# merci_main.net
KiCad netlist of a schematic drawn in Altium Designer
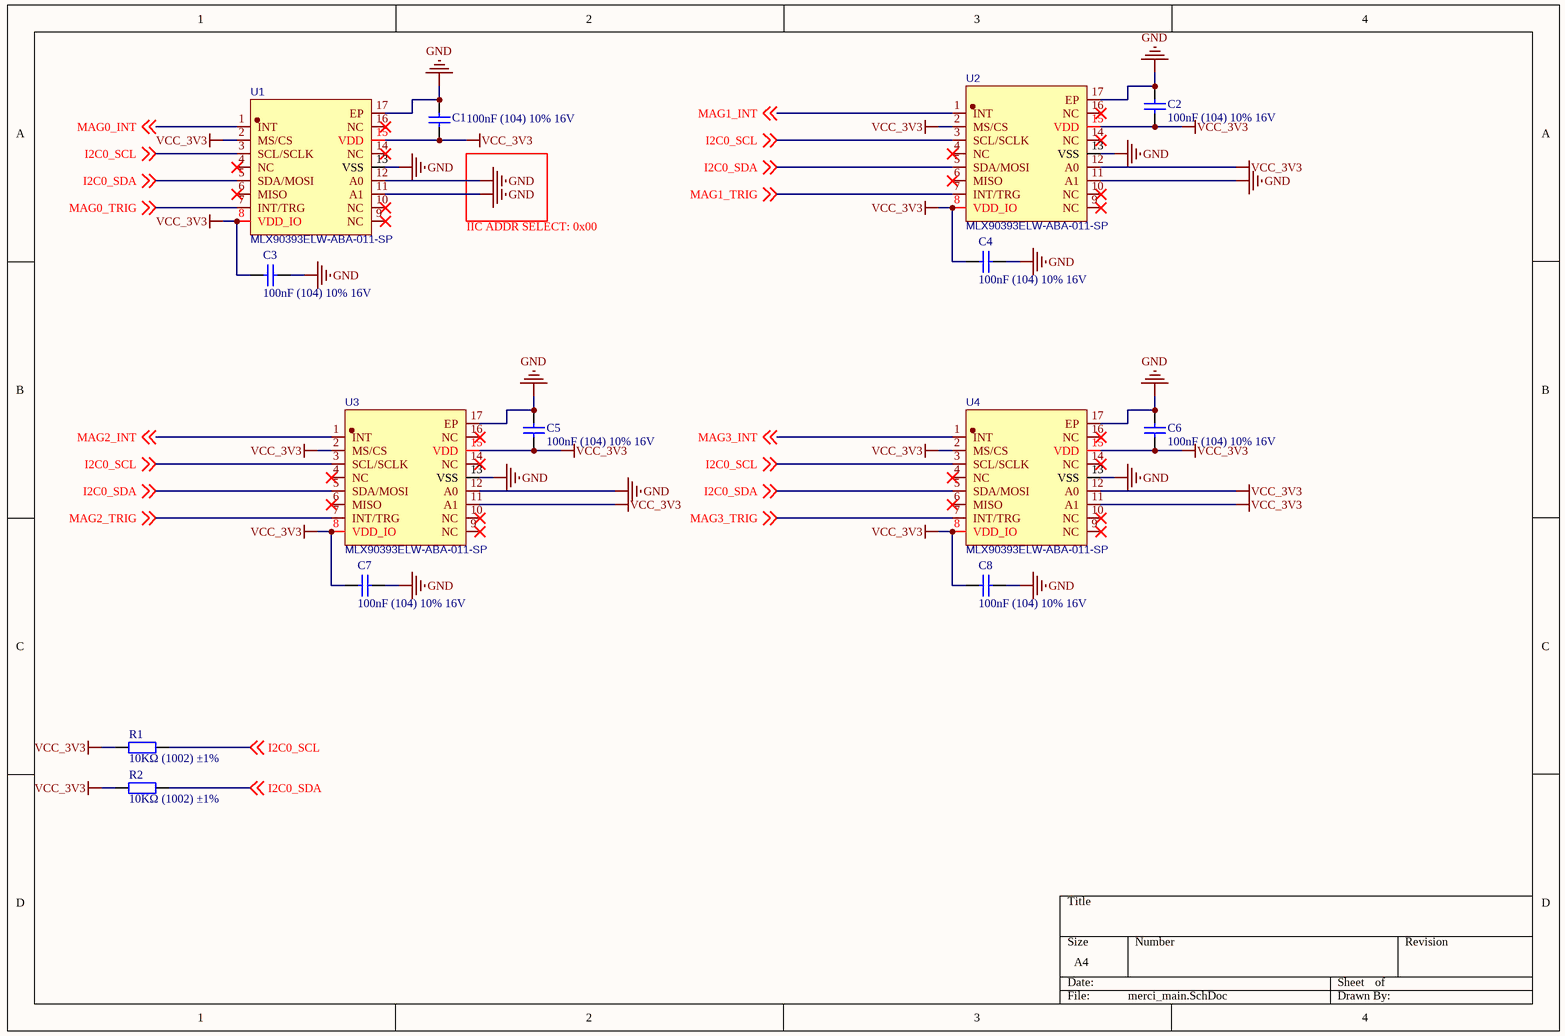
[diagram p0: merci_main.SchDoc]

(export (version "E")
  (design (tool "Eeschema 10.0.6"))
  (components
    (comp (ref "C1")
      (value "100nF (104) 10% 16V")
      (footprint "LC-0402_C_NOSILK")
      (description "贴片电容")
      (libsource (lib "Miscellaneous Devices LC") (part "0402 100nF (104) 10% 16V"))
    )
    (comp (ref "C2")
      (value "100nF (104) 10% 16V")
      (footprint "LC-0402_C_NOSILK")
      (description "贴片电容")
      (libsource (lib "Miscellaneous Devices LC") (part "0402 100nF (104) 10% 16V"))
    )
    (comp (ref "C3")
      (value "100nF (104) 10% 16V")
      (footprint "LC-0402_C_NOSILK")
      (description "贴片电容")
      (libsource (lib "Miscellaneous Devices LC") (part "0402 100nF (104) 10% 16V"))
    )
    (comp (ref "C4")
      (value "100nF (104) 10% 16V")
      (footprint "LC-0402_C_NOSILK")
      (description "贴片电容")
      (libsource (lib "Miscellaneous Devices LC") (part "0402 100nF (104) 10% 16V"))
    )
    (comp (ref "C5")
      (value "100nF (104) 10% 16V")
      (footprint "LC-0402_C_NOSILK")
      (description "贴片电容")
      (libsource (lib "Miscellaneous Devices LC") (part "0402 100nF (104) 10% 16V"))
    )
    (comp (ref "C6")
      (value "100nF (104) 10% 16V")
      (footprint "LC-0402_C_NOSILK")
      (description "贴片电容")
      (libsource (lib "Miscellaneous Devices LC") (part "0402 100nF (104) 10% 16V"))
    )
    (comp (ref "C7")
      (value "100nF (104) 10% 16V")
      (footprint "LC-0402_C_NOSILK")
      (description "贴片电容")
      (libsource (lib "Miscellaneous Devices LC") (part "0402 100nF (104) 10% 16V"))
    )
    (comp (ref "C8")
      (value "100nF (104) 10% 16V")
      (footprint "LC-0402_C_NOSILK")
      (description "贴片电容")
      (libsource (lib "Miscellaneous Devices LC") (part "0402 100nF (104) 10% 16V"))
    )
    (comp (ref "R1")
      (value "10KΩ (1002) ±1%")
      (footprint "LC-0402_R_NOSILK")
      (description "贴片电阻")
      (libsource (lib "Miscellaneous Devices LC") (part "0402 10KΩ (1002) 1%"))
    )
    (comp (ref "R2")
      (value "10KΩ (1002) ±1%")
      (footprint "LC-0402_R_NOSILK")
      (description "贴片电阻")
      (libsource (lib "Miscellaneous Devices LC") (part "0402 10KΩ (1002) 1%"))
    )
    (comp (ref "U1")
      (value "MLX90393ELW-ABA-011-SP")
      (footprint "QFN-16_L3.0-W3.0-P0.50-TR-EP1.7")
      (fields (field (name "BOM_SUPPLIER PART") "C1526586") (field (name "CONTRIBUTOR") "LCSC"))
      (libsource (lib "merci") (part "MLX90393ELW-ABA-011-SP"))
    )
    (comp (ref "U2")
      (value "MLX90393ELW-ABA-011-SP")
      (footprint "QFN-16_L3.0-W3.0-P0.50-TR-EP1.7")
      (fields (field (name "BOM_SUPPLIER PART") "C1526586") (field (name "CONTRIBUTOR") "LCSC"))
      (libsource (lib "merci") (part "MLX90393ELW-ABA-011-SP"))
    )
    (comp (ref "U3")
      (value "MLX90393ELW-ABA-011-SP")
      (footprint "QFN-16_L3.0-W3.0-P0.50-TR-EP1.7")
      (fields (field (name "BOM_SUPPLIER PART") "C1526586") (field (name "CONTRIBUTOR") "LCSC"))
      (libsource (lib "merci") (part "MLX90393ELW-ABA-011-SP"))
    )
    (comp (ref "U4")
      (value "MLX90393ELW-ABA-011-SP")
      (footprint "QFN-16_L3.0-W3.0-P0.50-TR-EP1.7")
      (fields (field (name "BOM_SUPPLIER PART") "C1526586") (field (name "CONTRIBUTOR") "LCSC"))
      (libsource (lib "merci") (part "MLX90393ELW-ABA-011-SP"))
    )
  )
  (nets
    (net (code "1") (name "GND") (class "Default")
      (node (ref "C1") (pin "2") (pinfunction "2_2") (pintype "passive"))
      (node (ref "C2") (pin "1") (pinfunction "1_1") (pintype "passive"))
      (node (ref "C3") (pin "1") (pinfunction "1_1") (pintype "passive"))
      (node (ref "C4") (pin "1") (pinfunction "1_1") (pintype "passive"))
      (node (ref "C5") (pin "2") (pinfunction "2_2") (pintype "passive"))
      (node (ref "C6") (pin "1") (pinfunction "1_1") (pintype "passive"))
      (node (ref "C7") (pin "1") (pinfunction "1_1") (pintype "passive"))
      (node (ref "C8") (pin "1") (pinfunction "1_1") (pintype "passive"))
      (node (ref "U1") (pin "11") (pinfunction "A1_11") (pintype "passive"))
      (node (ref "U1") (pin "12") (pinfunction "A0_12") (pintype "passive"))
      (node (ref "U1") (pin "13") (pinfunction "VSS_13") (pintype "passive"))
      (node (ref "U1") (pin "17") (pinfunction "EP_17") (pintype "passive"))
      (node (ref "U2") (pin "11") (pinfunction "A1_11") (pintype "passive"))
      (node (ref "U2") (pin "13") (pinfunction "VSS_13") (pintype "passive"))
      (node (ref "U2") (pin "17") (pinfunction "EP_17") (pintype "passive"))
      (node (ref "U3") (pin "12") (pinfunction "A0_12") (pintype "passive"))
      (node (ref "U3") (pin "13") (pinfunction "VSS_13") (pintype "passive"))
      (node (ref "U3") (pin "17") (pinfunction "EP_17") (pintype "passive"))
      (node (ref "U4") (pin "13") (pinfunction "VSS_13") (pintype "passive"))
      (node (ref "U4") (pin "17") (pinfunction "EP_17") (pintype "passive"))
    )
    (net (code "2") (name "I2C0_SCL") (class "Default")
      (node (ref "R1") (pin "2") (pinfunction "2_2") (pintype "passive"))
      (node (ref "U1") (pin "3") (pinfunction "SCL/SCLK_3") (pintype "passive"))
      (node (ref "U2") (pin "3") (pinfunction "SCL/SCLK_3") (pintype "passive"))
      (node (ref "U3") (pin "3") (pinfunction "SCL/SCLK_3") (pintype "passive"))
      (node (ref "U4") (pin "3") (pinfunction "SCL/SCLK_3") (pintype "passive"))
    )
    (net (code "3") (name "I2C0_SDA") (class "Default")
      (node (ref "R2") (pin "2") (pinfunction "2_2") (pintype "passive"))
      (node (ref "U1") (pin "5") (pinfunction "SDA/MOSI_5") (pintype "passive"))
      (node (ref "U2") (pin "5") (pinfunction "SDA/MOSI_5") (pintype "passive"))
      (node (ref "U3") (pin "5") (pinfunction "SDA/MOSI_5") (pintype "passive"))
      (node (ref "U4") (pin "5") (pinfunction "SDA/MOSI_5") (pintype "passive"))
    )
    (net (code "4") (name "MAG0_INT") (class "Default")
      (node (ref "U1") (pin "1") (pinfunction "INT_1") (pintype "passive"))
    )
    (net (code "5") (name "MAG0_TRIG") (class "Default")
      (node (ref "U1") (pin "7") (pinfunction "INT/TRG_7") (pintype "passive"))
    )
    (net (code "6") (name "MAG1_INT") (class "Default")
      (node (ref "U2") (pin "1") (pinfunction "INT_1") (pintype "passive"))
    )
    (net (code "7") (name "MAG1_TRIG") (class "Default")
      (node (ref "U2") (pin "7") (pinfunction "INT/TRG_7") (pintype "passive"))
    )
    (net (code "8") (name "MAG2_INT") (class "Default")
      (node (ref "U3") (pin "1") (pinfunction "INT_1") (pintype "passive"))
    )
    (net (code "9") (name "MAG2_TRIG") (class "Default")
      (node (ref "U3") (pin "7") (pinfunction "INT/TRG_7") (pintype "passive"))
    )
    (net (code "10") (name "MAG3_INT") (class "Default")
      (node (ref "U4") (pin "1") (pinfunction "INT_1") (pintype "passive"))
    )
    (net (code "11") (name "MAG3_TRIG") (class "Default")
      (node (ref "U4") (pin "7") (pinfunction "INT/TRG_7") (pintype "passive"))
    )
    (net (code "12") (name "VCC_3V3") (class "Default")
      (node (ref "C1") (pin "1") (pinfunction "1_1") (pintype "passive"))
      (node (ref "C2") (pin "2") (pinfunction "2_2") (pintype "passive"))
      (node (ref "C3") (pin "2") (pinfunction "2_2") (pintype "passive"))
      (node (ref "C4") (pin "2") (pinfunction "2_2") (pintype "passive"))
      (node (ref "C5") (pin "1") (pinfunction "1_1") (pintype "passive"))
      (node (ref "C6") (pin "2") (pinfunction "2_2") (pintype "passive"))
      (node (ref "C7") (pin "2") (pinfunction "2_2") (pintype "passive"))
      (node (ref "C8") (pin "2") (pinfunction "2_2") (pintype "passive"))
      (node (ref "R1") (pin "1") (pinfunction "1_1") (pintype "passive"))
      (node (ref "R2") (pin "1") (pinfunction "1_1") (pintype "passive"))
      (node (ref "U1") (pin "15") (pinfunction "VDD_15") (pintype "passive"))
      (node (ref "U1") (pin "2") (pinfunction "MS/CS_2") (pintype "passive"))
      (node (ref "U1") (pin "8") (pinfunction "VDD_IO_8") (pintype "passive"))
      (node (ref "U2") (pin "12") (pinfunction "A0_12") (pintype "passive"))
      (node (ref "U2") (pin "15") (pinfunction "VDD_15") (pintype "passive"))
      (node (ref "U2") (pin "2") (pinfunction "MS/CS_2") (pintype "passive"))
      (node (ref "U2") (pin "8") (pinfunction "VDD_IO_8") (pintype "passive"))
      (node (ref "U3") (pin "11") (pinfunction "A1_11") (pintype "passive"))
      (node (ref "U3") (pin "15") (pinfunction "VDD_15") (pintype "passive"))
      (node (ref "U3") (pin "2") (pinfunction "MS/CS_2") (pintype "passive"))
      (node (ref "U3") (pin "8") (pinfunction "VDD_IO_8") (pintype "passive"))
      (node (ref "U4") (pin "11") (pinfunction "A1_11") (pintype "passive"))
      (node (ref "U4") (pin "12") (pinfunction "A0_12") (pintype "passive"))
      (node (ref "U4") (pin "15") (pinfunction "VDD_15") (pintype "passive"))
      (node (ref "U4") (pin "2") (pinfunction "MS/CS_2") (pintype "passive"))
      (node (ref "U4") (pin "8") (pinfunction "VDD_IO_8") (pintype "passive"))
    )
    (net (code "13") (name "unconnected-(U1-MISO-Pad6)") (class "Default")
      (node (ref "U1") (pin "6") (pinfunction "MISO_6") (pintype "passive+no_connect"))
    )
    (net (code "14") (name "unconnected-(U1-NC-Pad4)") (class "Default")
      (node (ref "U1") (pin "4") (pinfunction "NC_4") (pintype "passive+no_connect"))
    )
    (net (code "15") (name "unconnected-(U1-NC-Pad9)") (class "Default")
      (node (ref "U1") (pin "9") (pinfunction "NC_9") (pintype "passive+no_connect"))
    )
    (net (code "16") (name "unconnected-(U1-NC-Pad10)") (class "Default")
      (node (ref "U1") (pin "10") (pinfunction "NC_10") (pintype "passive+no_connect"))
    )
    (net (code "17") (name "unconnected-(U1-NC-Pad14)") (class "Default")
      (node (ref "U1") (pin "14") (pinfunction "NC_14") (pintype "passive+no_connect"))
    )
    (net (code "18") (name "unconnected-(U1-NC-Pad16)") (class "Default")
      (node (ref "U1") (pin "16") (pinfunction "NC_16") (pintype "passive+no_connect"))
    )
    (net (code "19") (name "unconnected-(U2-MISO-Pad6)") (class "Default")
      (node (ref "U2") (pin "6") (pinfunction "MISO_6") (pintype "passive+no_connect"))
    )
    (net (code "20") (name "unconnected-(U2-NC-Pad4)") (class "Default")
      (node (ref "U2") (pin "4") (pinfunction "NC_4") (pintype "passive+no_connect"))
    )
    (net (code "21") (name "unconnected-(U2-NC-Pad9)") (class "Default")
      (node (ref "U2") (pin "9") (pinfunction "NC_9") (pintype "passive+no_connect"))
    )
    (net (code "22") (name "unconnected-(U2-NC-Pad10)") (class "Default")
      (node (ref "U2") (pin "10") (pinfunction "NC_10") (pintype "passive+no_connect"))
    )
    (net (code "23") (name "unconnected-(U2-NC-Pad14)") (class "Default")
      (node (ref "U2") (pin "14") (pinfunction "NC_14") (pintype "passive+no_connect"))
    )
    (net (code "24") (name "unconnected-(U2-NC-Pad16)") (class "Default")
      (node (ref "U2") (pin "16") (pinfunction "NC_16") (pintype "passive+no_connect"))
    )
    (net (code "25") (name "unconnected-(U3-MISO-Pad6)") (class "Default")
      (node (ref "U3") (pin "6") (pinfunction "MISO_6") (pintype "passive+no_connect"))
    )
    (net (code "26") (name "unconnected-(U3-NC-Pad4)") (class "Default")
      (node (ref "U3") (pin "4") (pinfunction "NC_4") (pintype "passive+no_connect"))
    )
    (net (code "27") (name "unconnected-(U3-NC-Pad9)") (class "Default")
      (node (ref "U3") (pin "9") (pinfunction "NC_9") (pintype "passive+no_connect"))
    )
    (net (code "28") (name "unconnected-(U3-NC-Pad10)") (class "Default")
      (node (ref "U3") (pin "10") (pinfunction "NC_10") (pintype "passive+no_connect"))
    )
    (net (code "29") (name "unconnected-(U3-NC-Pad14)") (class "Default")
      (node (ref "U3") (pin "14") (pinfunction "NC_14") (pintype "passive+no_connect"))
    )
    (net (code "30") (name "unconnected-(U3-NC-Pad16)") (class "Default")
      (node (ref "U3") (pin "16") (pinfunction "NC_16") (pintype "passive+no_connect"))
    )
    (net (code "31") (name "unconnected-(U4-MISO-Pad6)") (class "Default")
      (node (ref "U4") (pin "6") (pinfunction "MISO_6") (pintype "passive+no_connect"))
    )
    (net (code "32") (name "unconnected-(U4-NC-Pad4)") (class "Default")
      (node (ref "U4") (pin "4") (pinfunction "NC_4") (pintype "passive+no_connect"))
    )
    (net (code "33") (name "unconnected-(U4-NC-Pad9)") (class "Default")
      (node (ref "U4") (pin "9") (pinfunction "NC_9") (pintype "passive+no_connect"))
    )
    (net (code "34") (name "unconnected-(U4-NC-Pad10)") (class "Default")
      (node (ref "U4") (pin "10") (pinfunction "NC_10") (pintype "passive+no_connect"))
    )
    (net (code "35") (name "unconnected-(U4-NC-Pad14)") (class "Default")
      (node (ref "U4") (pin "14") (pinfunction "NC_14") (pintype "passive+no_connect"))
    )
    (net (code "36") (name "unconnected-(U4-NC-Pad16)") (class "Default")
      (node (ref "U4") (pin "16") (pinfunction "NC_16") (pintype "passive+no_connect"))
    )
  )
)
